# DUALPOWERS.net
KiCad netlist of a schematic drawn in EAGLE
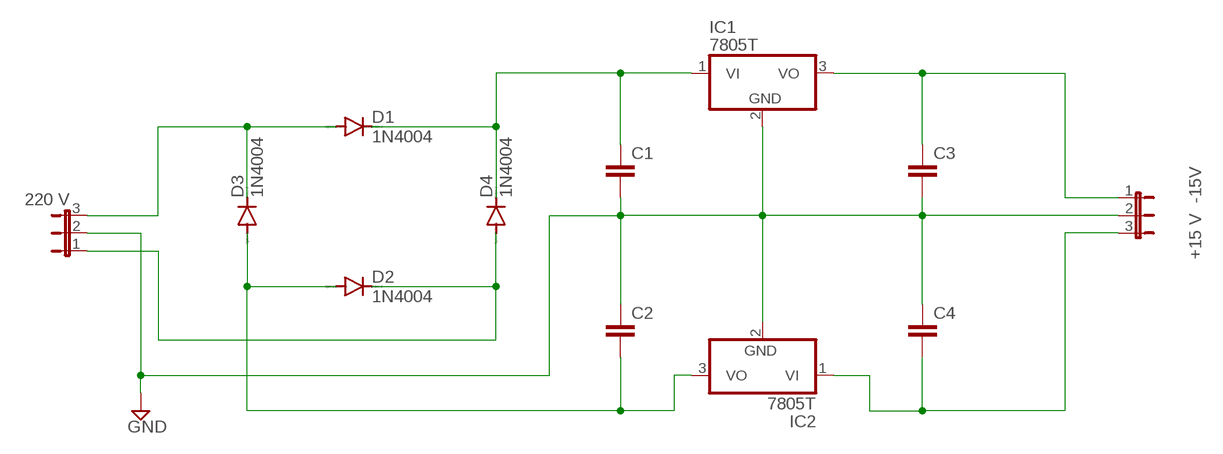
[diagram p0: schematic, sheet 1]

(export (version "E")
  (design (tool "Eeschema 10.0.6"))
  (components
    (comp (ref "-5V_GND_+5V")
      (value "+15 V -15V")
      (footprint "eagle-import:JP2")
      (libsource (lib "eagle-import") (part "JP2E"))
    )
    (comp (ref "C1")
      (value "C2,5-3")
      (footprint "eagle-import:C2.5-3")
      (libsource (lib "eagle-import") (part "C2,5-3"))
    )
    (comp (ref "C2")
      (value "C2,5-3")
      (footprint "eagle-import:C2.5-3")
      (libsource (lib "eagle-import") (part "C2,5-3"))
    )
    (comp (ref "C3")
      (value "C2,5-3")
      (footprint "eagle-import:C2.5-3")
      (libsource (lib "eagle-import") (part "C2,5-3"))
    )
    (comp (ref "C4")
      (value "C2,5-3")
      (footprint "eagle-import:C2.5-3")
      (libsource (lib "eagle-import") (part "C2,5-3"))
    )
    (comp (ref "D1")
      (value "1N4004")
      (footprint "eagle-import:DO41-10")
      (libsource (lib "eagle-import") (part "1N4004"))
    )
    (comp (ref "D2")
      (value "1N4004")
      (footprint "eagle-import:DO41-10")
      (libsource (lib "eagle-import") (part "1N4004"))
    )
    (comp (ref "D3")
      (value "1N4004")
      (footprint "eagle-import:DO41-10")
      (libsource (lib "eagle-import") (part "1N4004"))
    )
    (comp (ref "D4")
      (value "1N4004")
      (footprint "eagle-import:DO41-10")
      (libsource (lib "eagle-import") (part "1N4004"))
    )
    (comp (ref "IC1")
      (value "7805T")
      (footprint "eagle-import:TO220H")
      (libsource (lib "eagle-import") (part "78T05"))
    )
    (comp (ref "IC2")
      (value "7805T")
      (footprint "eagle-import:TO220H")
      (libsource (lib "eagle-import") (part "78T05"))
    )
    (comp (ref "JMP")
      (value "220 V")
      (footprint "eagle-import:JP2")
      (libsource (lib "eagle-import") (part "JP2E"))
    )
  )
  (nets
    (net (code "1") (name "GND") (class "Default")
      (node (ref "-5V_GND_+5V") (pin "2") (pinfunction "2_2") (pintype "passive"))
      (node (ref "C1") (pin "2") (pinfunction "2_2") (pintype "passive"))
      (node (ref "C2") (pin "1") (pinfunction "1_1") (pintype "passive"))
      (node (ref "C3") (pin "2") (pinfunction "2_2") (pintype "passive"))
      (node (ref "C4") (pin "1") (pinfunction "1_1") (pintype "passive"))
      (node (ref "IC1") (pin "2") (pinfunction "GND_2") (pintype "passive"))
      (node (ref "IC2") (pin "2") (pinfunction "GND_2") (pintype "passive"))
      (node (ref "JMP") (pin "2") (pinfunction "2_2") (pintype "passive"))
    )
    (net (code "2") (name "Net-(D1-PadA)") (class "Default")
      (node (ref "D1") (pin "A") (pinfunction "A_A") (pintype "passive"))
      (node (ref "D3") (pin "C") (pinfunction "C_C") (pintype "passive"))
      (node (ref "JMP") (pin "3") (pinfunction "3_3") (pintype "passive"))
    )
    (net (code "3") (name "Net-(D2-PadC)") (class "Default")
      (node (ref "D2") (pin "C") (pinfunction "C_C") (pintype "passive"))
      (node (ref "D4") (pin "A") (pinfunction "A_A") (pintype "passive"))
      (node (ref "JMP") (pin "1") (pinfunction "1_1") (pintype "passive"))
    )
    (net (code "4") (name "Net-(IC1-VI)") (class "Default")
      (node (ref "C1") (pin "1") (pinfunction "1_1") (pintype "passive"))
      (node (ref "D1") (pin "C") (pinfunction "C_C") (pintype "passive"))
      (node (ref "D4") (pin "C") (pinfunction "C_C") (pintype "passive"))
      (node (ref "IC1") (pin "1") (pinfunction "VI_1") (pintype "input"))
    )
    (net (code "5") (name "Net-(IC1-VO)") (class "Default")
      (node (ref "-5V_GND_+5V") (pin "1") (pinfunction "1_1") (pintype "passive"))
      (node (ref "C3") (pin "1") (pinfunction "1_1") (pintype "passive"))
      (node (ref "IC1") (pin "3") (pinfunction "VO_3") (pintype "passive"))
    )
    (net (code "6") (name "Net-(IC2-VI)") (class "Default")
      (node (ref "-5V_GND_+5V") (pin "3") (pinfunction "3_3") (pintype "passive"))
      (node (ref "C4") (pin "2") (pinfunction "2_2") (pintype "passive"))
      (node (ref "IC2") (pin "1") (pinfunction "VI_1") (pintype "input"))
    )
    (net (code "7") (name "Net-(IC2-VO)") (class "Default")
      (node (ref "C2") (pin "2") (pinfunction "2_2") (pintype "passive"))
      (node (ref "D2") (pin "A") (pinfunction "A_A") (pintype "passive"))
      (node (ref "D3") (pin "A") (pinfunction "A_A") (pintype "passive"))
      (node (ref "IC2") (pin "3") (pinfunction "VO_3") (pintype "passive"))
    )
  )
)
